# S3C_SplitSPI.net
KiCad netlist of a schematic drawn in Altium Designer
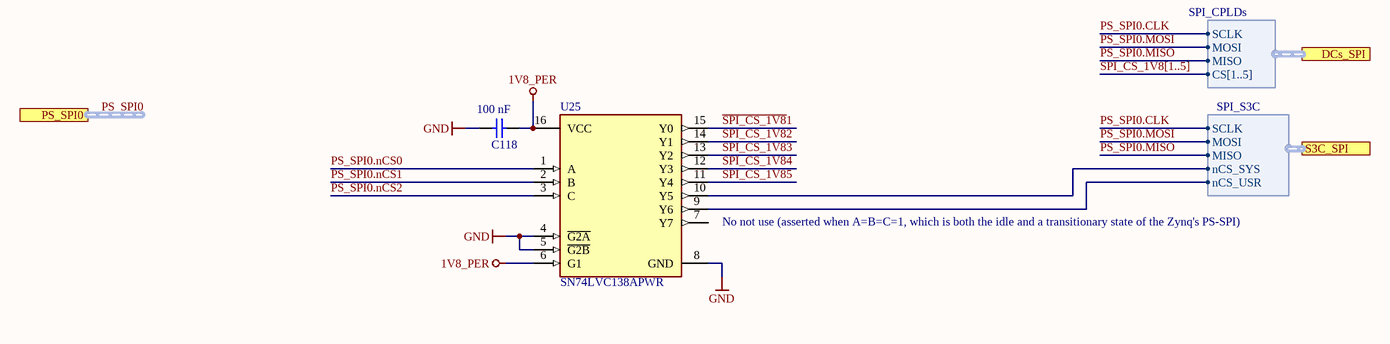
[diagram p0: S3C_SplitSPI.SchDoc]

(export (version "E")
  (design (tool "Eeschema 10.0.6"))
  (components
    (comp (ref "C118")
      (value "100 nF")
      (footprint "C_0603_TE")
      (description "Generic capacitor")
      (fields
        (field (name "MANUFACTURER PART NUMBER") "UZgen_C_0603_100nF_50V_X7R")
        (field (name "MANUFACTURER") "UZgen")
        (field (name "CREATED FROM") "AGeiger")
      )
      (libsource (lib "user") (part "CAP-NP"))
    )
    (comp (ref "U25")
      (value "SN74LVC138APWR")
      (footprint "TSSOP-16")
      (description "3-Line to 8-Line Decoders Demultiplexers")
      (fields
        (field (name "MANUFACTURER") "Texas Instruments")
        (field (name "LCSC PART NUMBER") "C485077")
        (field (name "CREATED FROM") "FRosner")
      )
      (libsource (lib "user") (part "SN74LVC138APWR"))
    )
  )
  (nets
    (net (code "7") (name "/PS_SPI0.nCS0") (class "Default")
      (node (ref "U25") (pin "1") (pinfunction "A_1") (pintype "input"))
    )
    (net (code "8") (name "/PS_SPI0.nCS1") (class "Default")
      (node (ref "U25") (pin "2") (pinfunction "B_2") (pintype "input"))
    )
    (net (code "9") (name "/PS_SPI0.nCS2") (class "Default")
      (node (ref "U25") (pin "3") (pinfunction "C_3") (pintype "input"))
    )
    (net (code "10") (name "/nCS_SYS") (class "Default")
      (node (ref "U25") (pin "10") (pinfunction "Y5_10") (pintype "output"))
    )
    (net (code "11") (name "/nCS_USR") (class "Default")
      (node (ref "U25") (pin "9") (pinfunction "Y6_9") (pintype "output"))
    )
    (net (code "15") (name "/~{SPI_CS_1V8}1") (class "Default")
      (node (ref "U25") (pin "15") (pinfunction "Y0_15") (pintype "output"))
    )
    (net (code "16") (name "/~{SPI_CS_1V8}2") (class "Default")
      (node (ref "U25") (pin "14") (pinfunction "Y1_14") (pintype "output"))
    )
    (net (code "17") (name "/~{SPI_CS_1V8}3") (class "Default")
      (node (ref "U25") (pin "13") (pinfunction "Y2_13") (pintype "output"))
    )
    (net (code "18") (name "/~{SPI_CS_1V8}4") (class "Default")
      (node (ref "U25") (pin "12") (pinfunction "Y3_12") (pintype "output"))
    )
    (net (code "19") (name "/~{SPI_CS_1V8}5") (class "Default")
      (node (ref "U25") (pin "11") (pinfunction "Y4_11") (pintype "output"))
    )
    (net (code "21") (name "1V8_PER") (class "Default")
      (node (ref "C118") (pin "2") (pinfunction "2_2") (pintype "passive"))
      (node (ref "U25") (pin "16") (pinfunction "VCC_16") (pintype "power_in"))
      (node (ref "U25") (pin "6") (pinfunction "G1_6") (pintype "input"))
    )
    (net (code "22") (name "GND") (class "Default")
      (node (ref "C118") (pin "1") (pinfunction "1_1") (pintype "passive"))
      (node (ref "U25") (pin "4") (pinfunction "~{G2A}_4") (pintype "input"))
      (node (ref "U25") (pin "5") (pinfunction "~{G2B}_5") (pintype "input"))
      (node (ref "U25") (pin "8") (pinfunction "GND_8") (pintype "power_in"))
    )
    (net (code "23") (name "unconnected-(U25-Y7-Pad7)") (class "Default")
      (node (ref "U25") (pin "7") (pinfunction "Y7_7") (pintype "output"))
    )
  )
)
